# bncs.net
KiCad netlist of a schematic drawn in Altium Designer
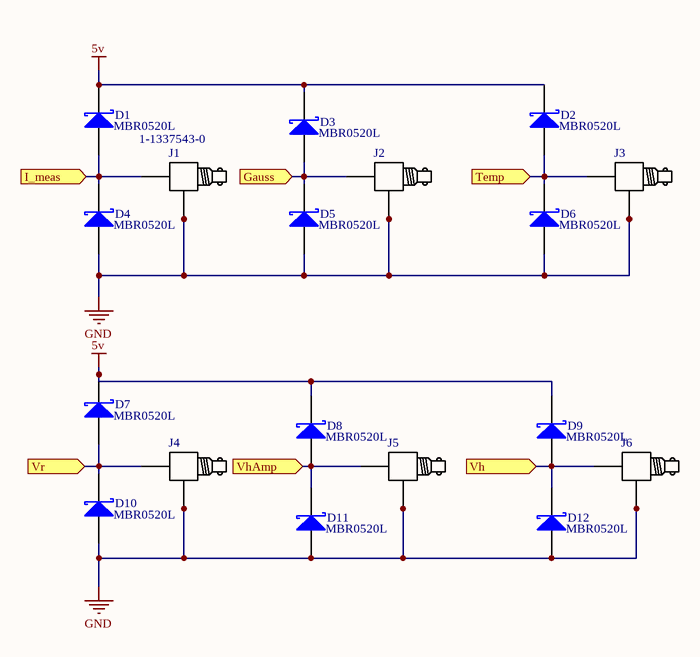
[diagram p0: bncs.SchDoc]

(export (version "E")
  (design (tool "Eeschema 10.0.6"))
  (components
    (comp (ref "D1")
      (value "~")
      (footprint "PBL - SMD Packages:SOD123")
      (description "Schottky Diode")
      (fields
        (field (name "SUPPLIER PART NUMBER 1") "MBR0520L")
        (field (name "MANUFACTURER") "FAIRCHILD SEMICONDUCTOR")
        (field (name "MANUFACTURER PART NUMBER") "MBR0520L")
        (field (name "PUBLISHER") "Altium Limited")
      )
      (libsource (lib "Miscellaneous Devices") (part "D Schottky"))
    )
    (comp (ref "D2")
      (value "~")
      (footprint "PBL - SMD Packages:SOD123")
      (description "Schottky Diode")
      (fields
        (field (name "SUPPLIER PART NUMBER 1") "MBR0520L")
        (field (name "MANUFACTURER") "FAIRCHILD SEMICONDUCTOR")
        (field (name "MANUFACTURER PART NUMBER") "MBR0520L")
        (field (name "PUBLISHER") "Altium Limited")
      )
      (libsource (lib "Miscellaneous Devices") (part "D Schottky"))
    )
    (comp (ref "D3")
      (value "~")
      (footprint "PBL - SMD Packages:SOD123")
      (description "Schottky Diode")
      (fields
        (field (name "SUPPLIER PART NUMBER 1") "MBR0520L")
        (field (name "MANUFACTURER") "FAIRCHILD SEMICONDUCTOR")
        (field (name "MANUFACTURER PART NUMBER") "MBR0520L")
        (field (name "PUBLISHER") "Altium Limited")
      )
      (libsource (lib "Miscellaneous Devices") (part "D Schottky"))
    )
    (comp (ref "D4")
      (value "~")
      (footprint "PBL - SMD Packages:SOD123")
      (description "Schottky Diode")
      (fields
        (field (name "SUPPLIER PART NUMBER 1") "MBR0520L")
        (field (name "MANUFACTURER") "FAIRCHILD SEMICONDUCTOR")
        (field (name "MANUFACTURER PART NUMBER") "MBR0520L")
        (field (name "PUBLISHER") "Altium Limited")
      )
      (libsource (lib "Miscellaneous Devices") (part "D Schottky"))
    )
    (comp (ref "D5")
      (value "~")
      (footprint "PBL - SMD Packages:SOD123")
      (description "Schottky Diode")
      (fields
        (field (name "SUPPLIER PART NUMBER 1") "MBR0520L")
        (field (name "MANUFACTURER") "FAIRCHILD SEMICONDUCTOR")
        (field (name "MANUFACTURER PART NUMBER") "MBR0520L")
        (field (name "PUBLISHER") "Altium Limited")
      )
      (libsource (lib "Miscellaneous Devices") (part "D Schottky"))
    )
    (comp (ref "D6")
      (value "~")
      (footprint "PBL - SMD Packages:SOD123")
      (description "Schottky Diode")
      (fields
        (field (name "SUPPLIER PART NUMBER 1") "MBR0520L")
        (field (name "MANUFACTURER") "FAIRCHILD SEMICONDUCTOR")
        (field (name "MANUFACTURER PART NUMBER") "MBR0520L")
        (field (name "PUBLISHER") "Altium Limited")
      )
      (libsource (lib "Miscellaneous Devices") (part "D Schottky"))
    )
    (comp (ref "D7")
      (value "~")
      (footprint "PBL - SMD Packages:SOD123")
      (description "Schottky Diode")
      (fields
        (field (name "SUPPLIER PART NUMBER 1") "MBR0520L")
        (field (name "MANUFACTURER") "FAIRCHILD SEMICONDUCTOR")
        (field (name "MANUFACTURER PART NUMBER") "MBR0520L")
        (field (name "PUBLISHER") "Altium Limited")
      )
      (libsource (lib "Miscellaneous Devices") (part "D Schottky"))
    )
    (comp (ref "D8")
      (value "~")
      (footprint "PBL - SMD Packages:SOD123")
      (description "Schottky Diode")
      (fields
        (field (name "SUPPLIER PART NUMBER 1") "MBR0520L")
        (field (name "MANUFACTURER") "FAIRCHILD SEMICONDUCTOR")
        (field (name "MANUFACTURER PART NUMBER") "MBR0520L")
        (field (name "PUBLISHER") "Altium Limited")
      )
      (libsource (lib "Miscellaneous Devices") (part "D Schottky"))
    )
    (comp (ref "D9")
      (value "~")
      (footprint "PBL - SMD Packages:SOD123")
      (description "Schottky Diode")
      (fields
        (field (name "SUPPLIER PART NUMBER 1") "MBR0520L")
        (field (name "MANUFACTURER") "FAIRCHILD SEMICONDUCTOR")
        (field (name "MANUFACTURER PART NUMBER") "MBR0520L")
        (field (name "PUBLISHER") "Altium Limited")
      )
      (libsource (lib "Miscellaneous Devices") (part "D Schottky"))
    )
    (comp (ref "D10")
      (value "~")
      (footprint "PBL - SMD Packages:SOD123")
      (description "Schottky Diode")
      (fields
        (field (name "SUPPLIER PART NUMBER 1") "MBR0520L")
        (field (name "MANUFACTURER") "FAIRCHILD SEMICONDUCTOR")
        (field (name "MANUFACTURER PART NUMBER") "MBR0520L")
        (field (name "PUBLISHER") "Altium Limited")
      )
      (libsource (lib "Miscellaneous Devices") (part "D Schottky"))
    )
    (comp (ref "D11")
      (value "~")
      (footprint "PBL - SMD Packages:SOD123")
      (description "Schottky Diode")
      (fields
        (field (name "SUPPLIER PART NUMBER 1") "MBR0520L")
        (field (name "MANUFACTURER") "FAIRCHILD SEMICONDUCTOR")
        (field (name "MANUFACTURER PART NUMBER") "MBR0520L")
        (field (name "PUBLISHER") "Altium Limited")
      )
      (libsource (lib "Miscellaneous Devices") (part "D Schottky"))
    )
    (comp (ref "D12")
      (value "~")
      (footprint "PBL - SMD Packages:SOD123")
      (description "Schottky Diode")
      (fields
        (field (name "SUPPLIER PART NUMBER 1") "MBR0520L")
        (field (name "MANUFACTURER") "FAIRCHILD SEMICONDUCTOR")
        (field (name "MANUFACTURER PART NUMBER") "MBR0520L")
        (field (name "PUBLISHER") "Altium Limited")
      )
      (libsource (lib "Miscellaneous Devices") (part "D Schottky"))
    )
    (comp (ref "J1")
      (value "~")
      (footprint "BNC-RA")
      (description "connector bnc")
      (fields
        (field (name "SUPPLIER PART NUMBER 1") "1-1337543-0")
        (field (name "MANUFACTURER") "TE CONNECTIVITY")
        (field (name "MANUFACTURER PART NUMBER") "1-1337543-0")
      )
      (libsource (lib "TH Connectors") (part "BNC-PCB-RA"))
    )
    (comp (ref "J2")
      (value "~")
      (footprint "BNC-RA")
      (description "connector bnc")
      (fields
        (field (name "MANUFACTURER") "TE CONNECTIVITY")
        (field (name "MANUFACTURER PART NUMBER") "1-1337543-0")
      )
      (libsource (lib "TH Connectors") (part "BNC-PCB-RA"))
    )
    (comp (ref "J3")
      (value "~")
      (footprint "BNC-RA")
      (description "connector bnc")
      (fields
        (field (name "MANUFACTURER") "TE CONNECTIVITY")
        (field (name "MANUFACTURER PART NUMBER") "1-1337543-0")
      )
      (libsource (lib "TH Connectors") (part "BNC-PCB-RA"))
    )
    (comp (ref "J4")
      (value "~")
      (footprint "BNC-RA")
      (description "connector bnc")
      (fields
        (field (name "MANUFACTURER") "TE CONNECTIVITY")
        (field (name "MANUFACTURER PART NUMBER") "1-1337543-0")
      )
      (libsource (lib "TH Connectors") (part "BNC-PCB-RA"))
    )
    (comp (ref "J5")
      (value "~")
      (footprint "BNC-RA")
      (description "connector bnc")
      (fields
        (field (name "MANUFACTURER") "TE CONNECTIVITY")
        (field (name "MANUFACTURER PART NUMBER") "1-1337543-0")
      )
      (libsource (lib "TH Connectors") (part "BNC-PCB-RA"))
    )
    (comp (ref "J6")
      (value "~")
      (footprint "BNC-RA")
      (description "connector bnc")
      (fields
        (field (name "MANUFACTURER") "TE CONNECTIVITY")
        (field (name "MANUFACTURER PART NUMBER") "1-1337543-0")
      )
      (libsource (lib "TH Connectors") (part "BNC-PCB-RA"))
    )
  )
  (nets
    (net (code "1") (name "/Gauss") (class "Default")
      (node (ref "D3") (pin "A") (pinfunction "A_A") (pintype "passive"))
      (node (ref "D5") (pin "K") (pinfunction "K_K") (pintype "passive"))
      (node (ref "J2") (pin "1") (pinfunction "1_1") (pintype "passive"))
    )
    (net (code "2") (name "/I_meas") (class "Default")
      (node (ref "D1") (pin "A") (pinfunction "A_A") (pintype "passive"))
      (node (ref "D4") (pin "K") (pinfunction "K_K") (pintype "passive"))
      (node (ref "J1") (pin "1") (pinfunction "1_1") (pintype "passive"))
    )
    (net (code "3") (name "/Temp") (class "Default")
      (node (ref "D2") (pin "A") (pinfunction "A_A") (pintype "passive"))
      (node (ref "D6") (pin "K") (pinfunction "K_K") (pintype "passive"))
      (node (ref "J3") (pin "1") (pinfunction "1_1") (pintype "passive"))
    )
    (net (code "4") (name "/Vh") (class "Default")
      (node (ref "D12") (pin "K") (pinfunction "K_K") (pintype "passive"))
      (node (ref "D9") (pin "A") (pinfunction "A_A") (pintype "passive"))
      (node (ref "J6") (pin "1") (pinfunction "1_1") (pintype "passive"))
    )
    (net (code "5") (name "/VhAmp") (class "Default")
      (node (ref "D11") (pin "K") (pinfunction "K_K") (pintype "passive"))
      (node (ref "D8") (pin "A") (pinfunction "A_A") (pintype "passive"))
      (node (ref "J5") (pin "1") (pinfunction "1_1") (pintype "passive"))
    )
    (net (code "6") (name "/Vr") (class "Default")
      (node (ref "D10") (pin "K") (pinfunction "K_K") (pintype "passive"))
      (node (ref "D7") (pin "A") (pinfunction "A_A") (pintype "passive"))
      (node (ref "J4") (pin "1") (pinfunction "1_1") (pintype "passive"))
    )
    (net (code "7") (name "5v") (class "Default")
      (node (ref "D1") (pin "K") (pinfunction "K_K") (pintype "passive"))
      (node (ref "D2") (pin "K") (pinfunction "K_K") (pintype "passive"))
      (node (ref "D3") (pin "K") (pinfunction "K_K") (pintype "passive"))
      (node (ref "D7") (pin "K") (pinfunction "K_K") (pintype "passive"))
      (node (ref "D8") (pin "K") (pinfunction "K_K") (pintype "passive"))
      (node (ref "D9") (pin "K") (pinfunction "K_K") (pintype "passive"))
    )
    (net (code "8") (name "GND") (class "Default")
      (node (ref "D10") (pin "A") (pinfunction "A_A") (pintype "passive"))
      (node (ref "D11") (pin "A") (pinfunction "A_A") (pintype "passive"))
      (node (ref "D12") (pin "A") (pinfunction "A_A") (pintype "passive"))
      (node (ref "D4") (pin "A") (pinfunction "A_A") (pintype "passive"))
      (node (ref "D5") (pin "A") (pinfunction "A_A") (pintype "passive"))
      (node (ref "D6") (pin "A") (pinfunction "A_A") (pintype "passive"))
      (node (ref "J1") (pin "2") (pinfunction "gnd_2") (pintype "passive"))
      (node (ref "J1") (pin "A") (pinfunction "A_A") (pintype "passive"))
      (node (ref "J1") (pin "B") (pinfunction "B_B") (pintype "passive"))
      (node (ref "J2") (pin "2") (pinfunction "gnd_2") (pintype "passive"))
      (node (ref "J2") (pin "A") (pinfunction "A_A") (pintype "passive"))
      (node (ref "J2") (pin "B") (pinfunction "B_B") (pintype "passive"))
      (node (ref "J3") (pin "2") (pinfunction "gnd_2") (pintype "passive"))
      (node (ref "J3") (pin "A") (pinfunction "A_A") (pintype "passive"))
      (node (ref "J3") (pin "B") (pinfunction "B_B") (pintype "passive"))
      (node (ref "J4") (pin "2") (pinfunction "gnd_2") (pintype "passive"))
      (node (ref "J4") (pin "A") (pinfunction "A_A") (pintype "passive"))
      (node (ref "J4") (pin "B") (pinfunction "B_B") (pintype "passive"))
      (node (ref "J5") (pin "2") (pinfunction "gnd_2") (pintype "passive"))
      (node (ref "J5") (pin "A") (pinfunction "A_A") (pintype "passive"))
      (node (ref "J5") (pin "B") (pinfunction "B_B") (pintype "passive"))
      (node (ref "J6") (pin "2") (pinfunction "gnd_2") (pintype "passive"))
      (node (ref "J6") (pin "A") (pinfunction "A_A") (pintype "passive"))
      (node (ref "J6") (pin "B") (pinfunction "B_B") (pintype "passive"))
    )
  )
)
